# WalkerStalkerv03.net
KiCad netlist of a schematic drawn in EAGLE
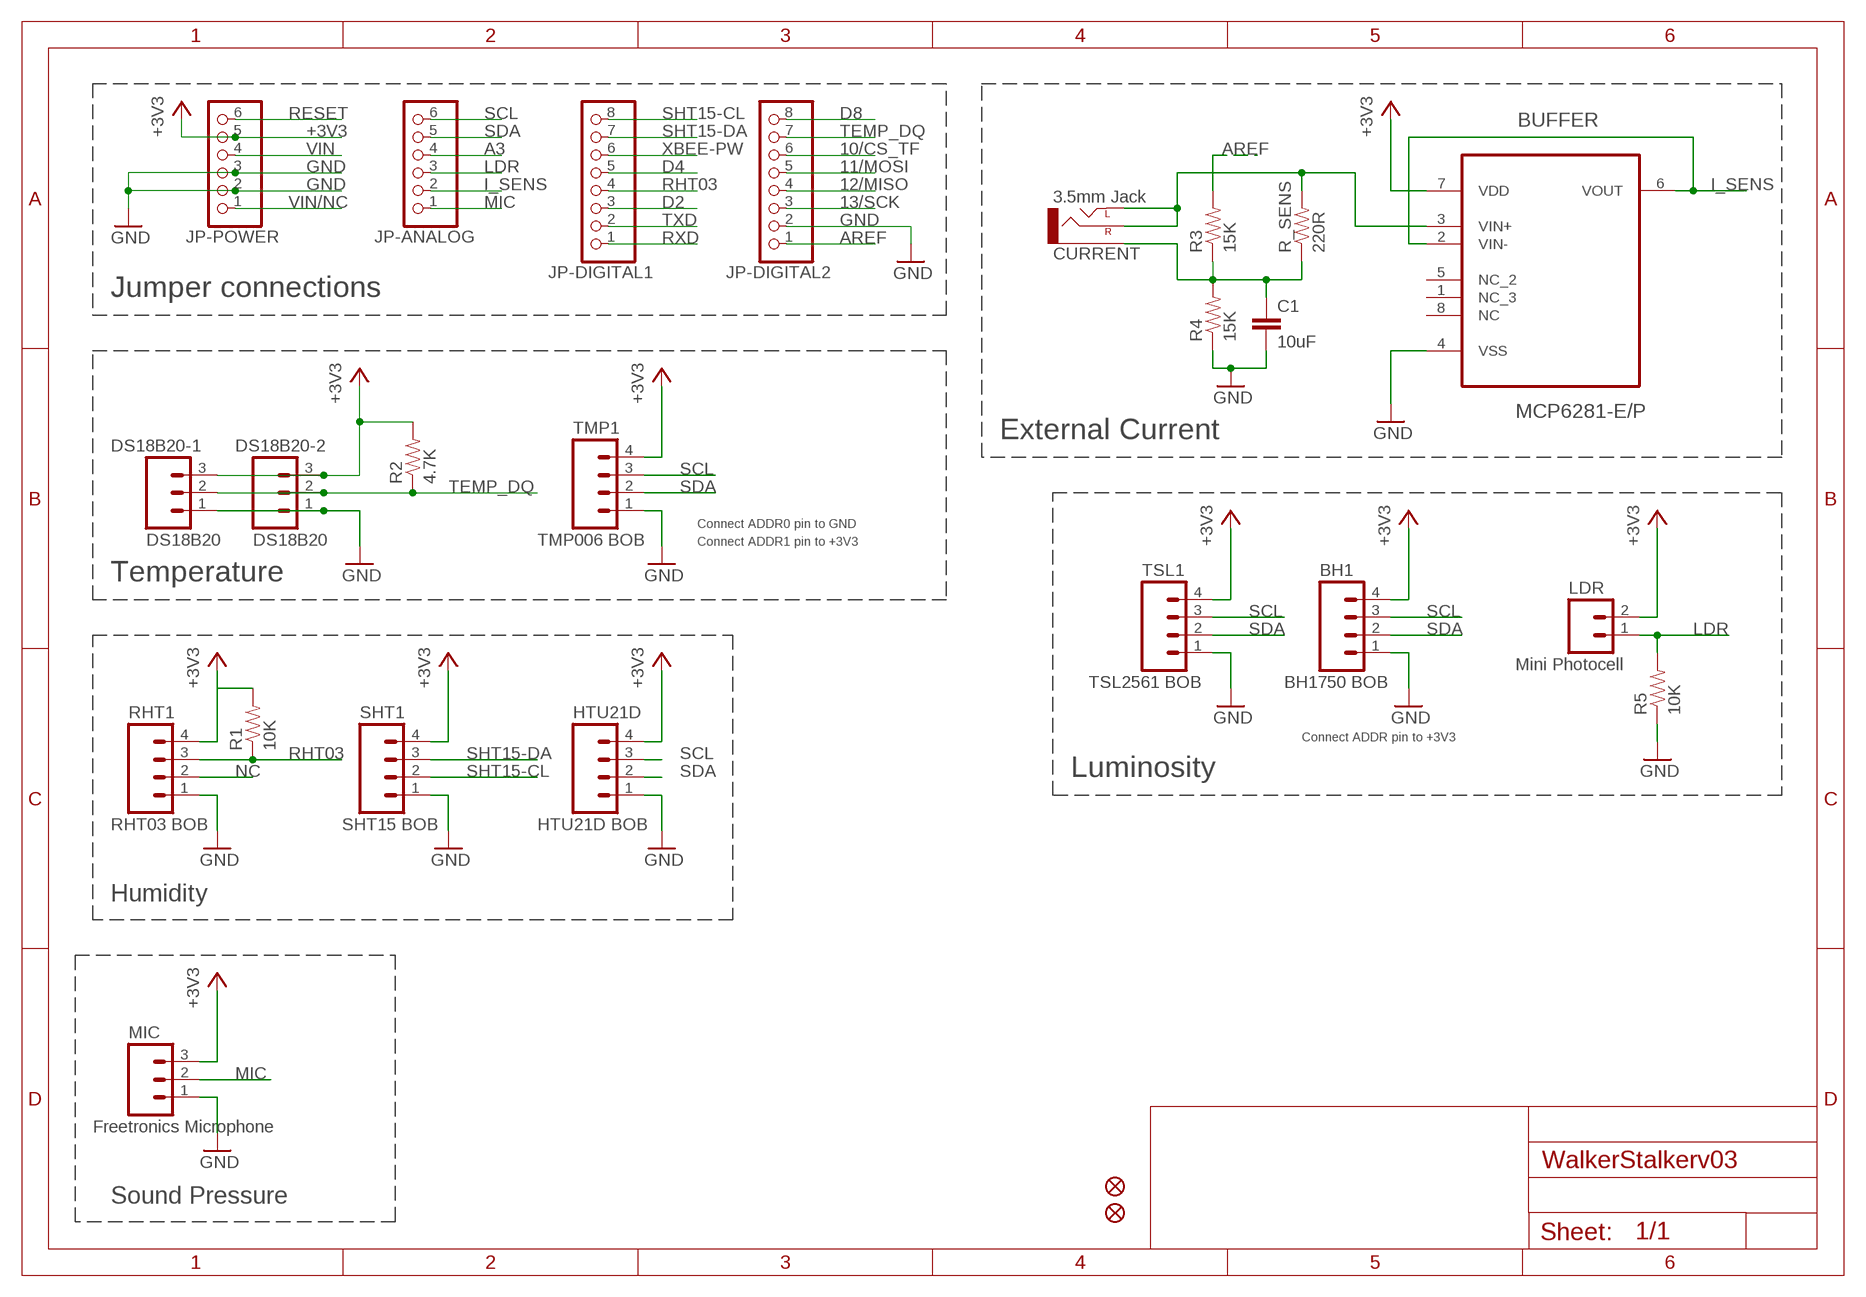
[diagram p0: schematic, sheet 1, part 1 of 2]
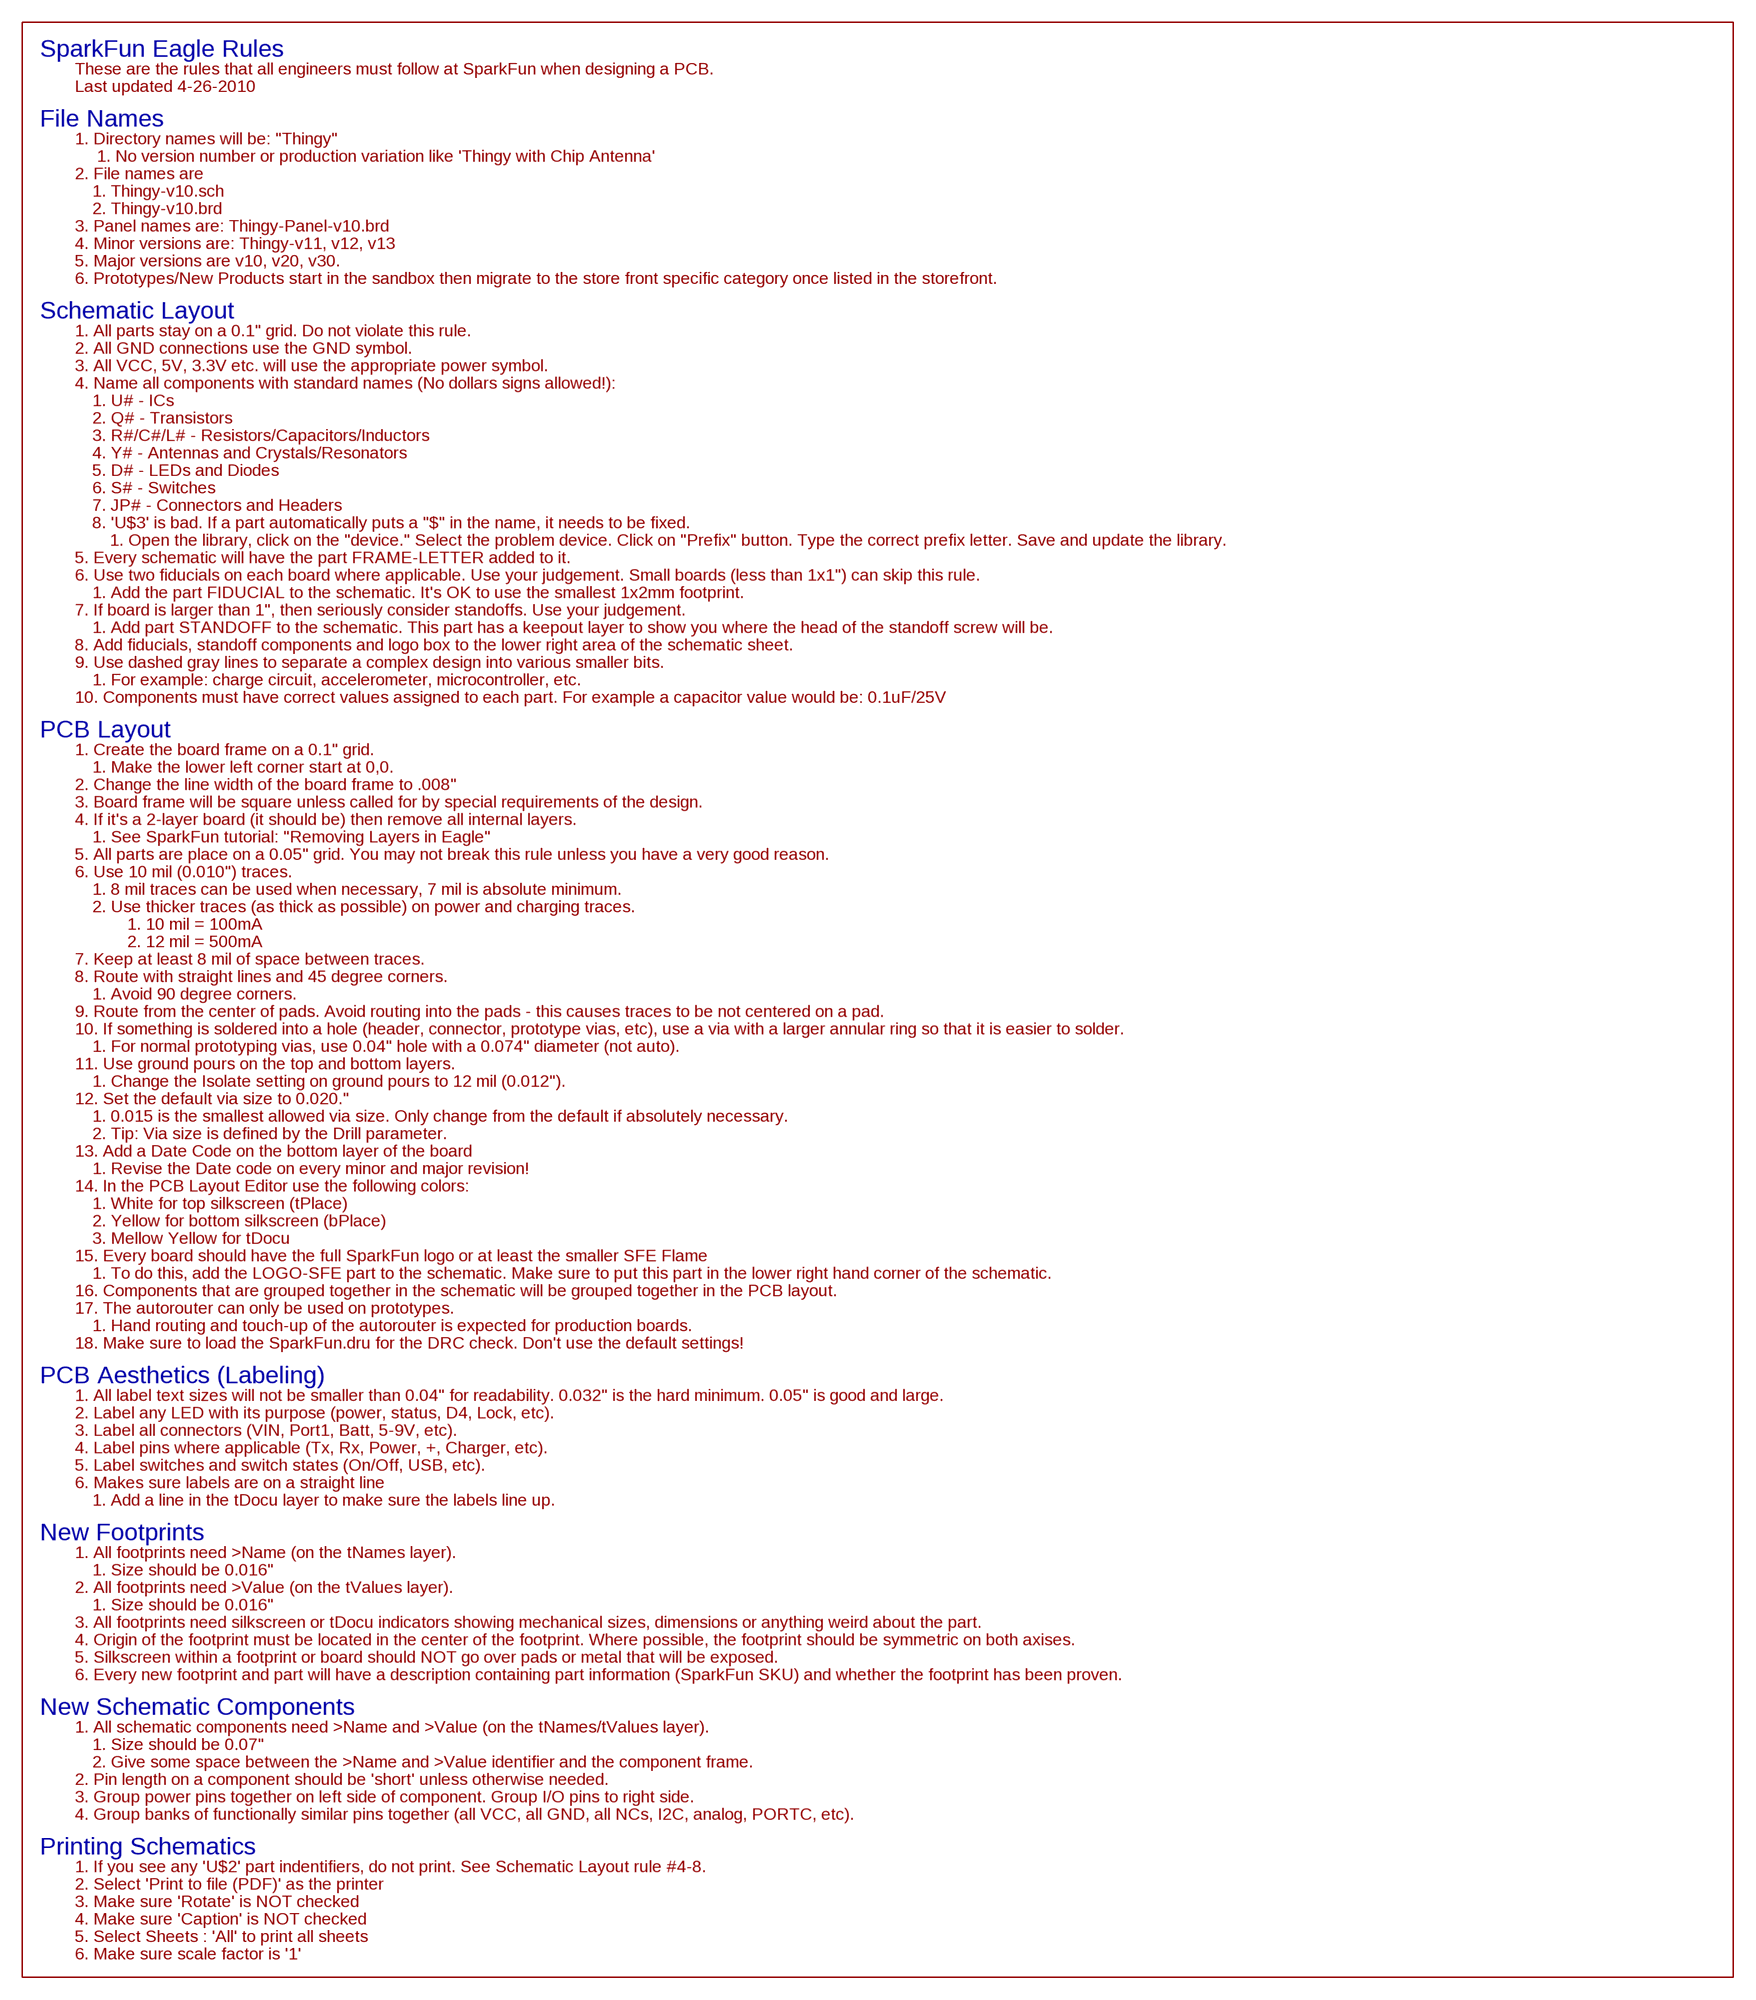
[diagram p1: schematic, sheet 1, part 2 of 2]

(export (version "E")
  (design (tool "Eeschema 10.0.6"))
  (components
    (comp (ref "BH1")
      (value "BH1750 BOB")
      (footprint "eagle-import:MOLEX-1X4")
      (libsource (lib "eagle-import") (part "M04POLAR"))
    )
    (comp (ref "BUFFER")
      (value "MCP6281-E/P")
      (footprint "eagle-import:DIP254P762X432-8")
      (libsource (lib "eagle-import") (part "MCP6281-E/P"))
    )
    (comp (ref "C1")
      (value "10uF")
      (footprint "eagle-import:1206")
      (libsource (lib "eagle-import") (part "CAP1206"))
    )
    (comp (ref "CURRENT")
      (value "3.5mm Jack")
      (footprint "eagle-import:AUDIO-JACK")
      (libsource (lib "eagle-import") (part "AUDIO-JACKPTH"))
    )
    (comp (ref "DS18B20-1")
      (value "DS18B20")
      (footprint "eagle-import:MOLEX-1X3")
      (libsource (lib "eagle-import") (part "M03POLAR"))
    )
    (comp (ref "DS18B20-2")
      (value "DS18B20")
      (footprint "eagle-import:MOLEX-1X3")
      (libsource (lib "eagle-import") (part "M03POLAR"))
    )
    (comp (ref "FID1")
      (value "FIDUCIAL1.5X3")
      (footprint "eagle-import:FIDUCIAL-1.5X3")
      (libsource (lib "eagle-import") (part "FIDUCIAL1.5X3"))
    )
    (comp (ref "FID2")
      (value "FIDUCIAL1.5X3")
      (footprint "eagle-import:FIDUCIAL-1.5X3")
      (libsource (lib "eagle-import") (part "FIDUCIAL1.5X3"))
    )
    (comp (ref "HTU21D")
      (value "HTU21D BOB")
      (footprint "eagle-import:MOLEX-1X4")
      (libsource (lib "eagle-import") (part "M04POLAR"))
    )
    (comp (ref "JP-ANALOG")
      (value "PINHD-1X6CB")
      (footprint "eagle-import:1X06-CLEANBIG")
      (libsource (lib "eagle-import") (part "PINHD-1X6CB"))
    )
    (comp (ref "JP-DIGITAL1")
      (value "PINHD-1X8CLEANBIG")
      (footprint "eagle-import:1X08-CLEANBIG")
      (libsource (lib "eagle-import") (part "PINHD-1X8CLEANBIG"))
    )
    (comp (ref "JP-DIGITAL2")
      (value "PINHD-1X8CLEANBIG")
      (footprint "eagle-import:1X08-CLEANBIG")
      (libsource (lib "eagle-import") (part "PINHD-1X8CLEANBIG"))
    )
    (comp (ref "JP-POWER")
      (value "PINHD-1X6CB")
      (footprint "eagle-import:1X06-CLEANBIG")
      (libsource (lib "eagle-import") (part "PINHD-1X6CB"))
    )
    (comp (ref "LDR")
      (value "Mini Photocell")
      (footprint "eagle-import:MOLEX-1X2")
      (libsource (lib "eagle-import") (part "M02POLAR"))
    )
    (comp (ref "MIC")
      (value "Freetronics Microphone")
      (footprint "eagle-import:MOLEX-1X3")
      (libsource (lib "eagle-import") (part "M03POLAR"))
    )
    (comp (ref "R1")
      (value "10K")
      (footprint "eagle-import:1206")
      (libsource (lib "eagle-import") (part "RESISTOR1206"))
    )
    (comp (ref "R2")
      (value "4.7K")
      (footprint "eagle-import:1206")
      (libsource (lib "eagle-import") (part "RESISTOR1206"))
    )
    (comp (ref "R3")
      (value "15K")
      (footprint "eagle-import:1206")
      (libsource (lib "eagle-import") (part "RESISTOR1206"))
    )
    (comp (ref "R4")
      (value "15K")
      (footprint "eagle-import:1206")
      (libsource (lib "eagle-import") (part "RESISTOR1206"))
    )
    (comp (ref "R5")
      (value "10K")
      (footprint "eagle-import:1206")
      (libsource (lib "eagle-import") (part "RESISTOR1206"))
    )
    (comp (ref "RHT1")
      (value "RHT03 BOB")
      (footprint "eagle-import:MOLEX-1X4")
      (libsource (lib "eagle-import") (part "M04POLAR"))
    )
    (comp (ref "R_SENS")
      (value "220R")
      (footprint "eagle-import:1206")
      (libsource (lib "eagle-import") (part "RESISTOR1206"))
    )
    (comp (ref "SHT1")
      (value "SHT15 BOB")
      (footprint "eagle-import:MOLEX-1X4")
      (libsource (lib "eagle-import") (part "M04POLAR"))
    )
    (comp (ref "TMP1")
      (value "TMP006 BOB")
      (footprint "eagle-import:MOLEX-1X4")
      (libsource (lib "eagle-import") (part "M04POLAR"))
    )
    (comp (ref "TSL1")
      (value "TSL2561 BOB")
      (footprint "eagle-import:MOLEX-1X4")
      (libsource (lib "eagle-import") (part "M04POLAR"))
    )
  )
  (nets
    (net (code "1") (name "+3V3") (class "Default")
      (node (ref "BH1") (pin "4") (pinfunction "4_4") (pintype "passive"))
      (node (ref "BUFFER") (pin "7") (pinfunction "VDD_7") (pintype "power_in"))
      (node (ref "DS18B20-1") (pin "3") (pinfunction "3_3") (pintype "passive"))
      (node (ref "DS18B20-2") (pin "3") (pinfunction "3_3") (pintype "passive"))
      (node (ref "HTU21D") (pin "4") (pinfunction "4_4") (pintype "passive"))
      (node (ref "JP-POWER") (pin "5") (pinfunction "5_5") (pintype "passive"))
      (node (ref "LDR") (pin "2") (pinfunction "2_2") (pintype "passive"))
      (node (ref "MIC") (pin "3") (pinfunction "3_3") (pintype "passive"))
      (node (ref "R1") (pin "2") (pinfunction "2_2") (pintype "passive"))
      (node (ref "R2") (pin "2") (pinfunction "2_2") (pintype "passive"))
      (node (ref "RHT1") (pin "4") (pinfunction "4_4") (pintype "passive"))
      (node (ref "SHT1") (pin "4") (pinfunction "4_4") (pintype "passive"))
      (node (ref "TMP1") (pin "4") (pinfunction "4_4") (pintype "passive"))
      (node (ref "TSL1") (pin "4") (pinfunction "4_4") (pintype "passive"))
    )
    (net (code "2") (name "/10{slash}CS_TF") (class "Default")
      (node (ref "JP-DIGITAL2") (pin "6") (pinfunction "6_6") (pintype "passive"))
    )
    (net (code "3") (name "/11{slash}MOSI") (class "Default")
      (node (ref "JP-DIGITAL2") (pin "5") (pinfunction "5_5") (pintype "passive"))
    )
    (net (code "4") (name "/12{slash}MISO") (class "Default")
      (node (ref "JP-DIGITAL2") (pin "4") (pinfunction "4_4") (pintype "passive"))
    )
    (net (code "5") (name "/13{slash}SCK") (class "Default")
      (node (ref "JP-DIGITAL2") (pin "3") (pinfunction "3_3") (pintype "passive"))
    )
    (net (code "6") (name "/A3") (class "Default")
      (node (ref "JP-ANALOG") (pin "4") (pinfunction "4_4") (pintype "passive"))
    )
    (net (code "7") (name "/AREF") (class "Default")
      (node (ref "JP-DIGITAL2") (pin "1") (pinfunction "1_1") (pintype "passive"))
      (node (ref "R3") (pin "2") (pinfunction "2_2") (pintype "passive"))
    )
    (net (code "8") (name "/D2") (class "Default")
      (node (ref "JP-DIGITAL1") (pin "3") (pinfunction "3_3") (pintype "passive"))
    )
    (net (code "9") (name "/D4") (class "Default")
      (node (ref "JP-DIGITAL1") (pin "5") (pinfunction "5_5") (pintype "passive"))
    )
    (net (code "10") (name "/D8") (class "Default")
      (node (ref "JP-DIGITAL2") (pin "8") (pinfunction "8_8") (pintype "passive"))
    )
    (net (code "11") (name "/I_SENS") (class "Default")
      (node (ref "BUFFER") (pin "2") (pinfunction "VIN-_2") (pintype "input"))
      (node (ref "BUFFER") (pin "6") (pinfunction "VOUT_6") (pintype "output"))
      (node (ref "JP-ANALOG") (pin "2") (pinfunction "2_2") (pintype "passive"))
    )
    (net (code "12") (name "/LDR") (class "Default")
      (node (ref "JP-ANALOG") (pin "3") (pinfunction "3_3") (pintype "passive"))
      (node (ref "LDR") (pin "1") (pinfunction "1_1") (pintype "passive"))
      (node (ref "R5") (pin "2") (pinfunction "2_2") (pintype "passive"))
    )
    (net (code "13") (name "/MIC") (class "Default")
      (node (ref "JP-ANALOG") (pin "1") (pinfunction "1_1") (pintype "passive"))
      (node (ref "MIC") (pin "2") (pinfunction "2_2") (pintype "passive"))
    )
    (net (code "14") (name "/NC") (class "Default")
      (node (ref "RHT1") (pin "2") (pinfunction "2_2") (pintype "passive"))
    )
    (net (code "15") (name "/RESET") (class "Default")
      (node (ref "JP-POWER") (pin "6") (pinfunction "6_6") (pintype "passive"))
    )
    (net (code "16") (name "/RHT03") (class "Default")
      (node (ref "JP-DIGITAL1") (pin "4") (pinfunction "4_4") (pintype "passive"))
      (node (ref "R1") (pin "1") (pinfunction "1_1") (pintype "passive"))
      (node (ref "RHT1") (pin "3") (pinfunction "3_3") (pintype "passive"))
    )
    (net (code "17") (name "/RXD") (class "Default")
      (node (ref "JP-DIGITAL1") (pin "1") (pinfunction "1_1") (pintype "passive"))
    )
    (net (code "18") (name "/SCL") (class "Default")
      (node (ref "BH1") (pin "3") (pinfunction "3_3") (pintype "passive"))
      (node (ref "HTU21D") (pin "3") (pinfunction "3_3") (pintype "passive"))
      (node (ref "JP-ANALOG") (pin "6") (pinfunction "6_6") (pintype "passive"))
      (node (ref "TMP1") (pin "3") (pinfunction "3_3") (pintype "passive"))
      (node (ref "TSL1") (pin "3") (pinfunction "3_3") (pintype "passive"))
    )
    (net (code "19") (name "/SDA") (class "Default")
      (node (ref "BH1") (pin "2") (pinfunction "2_2") (pintype "passive"))
      (node (ref "HTU21D") (pin "2") (pinfunction "2_2") (pintype "passive"))
      (node (ref "JP-ANALOG") (pin "5") (pinfunction "5_5") (pintype "passive"))
      (node (ref "TMP1") (pin "2") (pinfunction "2_2") (pintype "passive"))
      (node (ref "TSL1") (pin "2") (pinfunction "2_2") (pintype "passive"))
    )
    (net (code "20") (name "/SHT15-CL") (class "Default")
      (node (ref "JP-DIGITAL1") (pin "8") (pinfunction "8_8") (pintype "passive"))
      (node (ref "SHT1") (pin "2") (pinfunction "2_2") (pintype "passive"))
    )
    (net (code "21") (name "/SHT15-DA") (class "Default")
      (node (ref "JP-DIGITAL1") (pin "7") (pinfunction "7_7") (pintype "passive"))
      (node (ref "SHT1") (pin "3") (pinfunction "3_3") (pintype "passive"))
    )
    (net (code "22") (name "/TEMP_DQ") (class "Default")
      (node (ref "DS18B20-1") (pin "2") (pinfunction "2_2") (pintype "passive"))
      (node (ref "DS18B20-2") (pin "2") (pinfunction "2_2") (pintype "passive"))
      (node (ref "JP-DIGITAL2") (pin "7") (pinfunction "7_7") (pintype "passive"))
      (node (ref "R2") (pin "1") (pinfunction "1_1") (pintype "passive"))
    )
    (net (code "23") (name "/TXD") (class "Default")
      (node (ref "JP-DIGITAL1") (pin "2") (pinfunction "2_2") (pintype "passive"))
    )
    (net (code "24") (name "/VIN") (class "Default")
      (node (ref "JP-POWER") (pin "4") (pinfunction "4_4") (pintype "passive"))
    )
    (net (code "25") (name "/VIN{slash}NC") (class "Default")
      (node (ref "JP-POWER") (pin "1") (pinfunction "1_1") (pintype "passive"))
    )
    (net (code "26") (name "/XBEE-PW") (class "Default")
      (node (ref "JP-DIGITAL1") (pin "6") (pinfunction "6_6") (pintype "passive"))
    )
    (net (code "27") (name "GND") (class "Default")
      (node (ref "BH1") (pin "1") (pinfunction "1_1") (pintype "passive"))
      (node (ref "BUFFER") (pin "4") (pinfunction "VSS_4") (pintype "power_in"))
      (node (ref "C1") (pin "2") (pinfunction "2_2") (pintype "passive"))
      (node (ref "DS18B20-1") (pin "1") (pinfunction "1_1") (pintype "passive"))
      (node (ref "DS18B20-2") (pin "1") (pinfunction "1_1") (pintype "passive"))
      (node (ref "HTU21D") (pin "1") (pinfunction "1_1") (pintype "passive"))
      (node (ref "JP-DIGITAL2") (pin "2") (pinfunction "2_2") (pintype "passive"))
      (node (ref "JP-POWER") (pin "2") (pinfunction "2_2") (pintype "passive"))
      (node (ref "JP-POWER") (pin "3") (pinfunction "3_3") (pintype "passive"))
      (node (ref "MIC") (pin "1") (pinfunction "1_1") (pintype "passive"))
      (node (ref "R4") (pin "1") (pinfunction "1_1") (pintype "passive"))
      (node (ref "R5") (pin "1") (pinfunction "1_1") (pintype "passive"))
      (node (ref "RHT1") (pin "1") (pinfunction "1_1") (pintype "passive"))
      (node (ref "SHT1") (pin "1") (pinfunction "1_1") (pintype "passive"))
      (node (ref "TMP1") (pin "1") (pinfunction "1_1") (pintype "passive"))
      (node (ref "TSL1") (pin "1") (pinfunction "1_1") (pintype "passive"))
    )
    (net (code "28") (name "Net-(BUFFER-VIN+)") (class "Default")
      (node (ref "BUFFER") (pin "3") (pinfunction "VIN+_3") (pintype "input"))
      (node (ref "CURRENT") (pin "RING") (pinfunction "RIGHT_RING") (pintype "bidirectional"))
      (node (ref "CURRENT") (pin "TIP") (pinfunction "LEFT_TIP") (pintype "bidirectional"))
      (node (ref "R_SENS") (pin "2") (pinfunction "2_2") (pintype "passive"))
    )
    (net (code "29") (name "Net-(C1-Pad1)") (class "Default")
      (node (ref "C1") (pin "1") (pinfunction "1_1") (pintype "passive"))
      (node (ref "CURRENT") (pin "SLEEVE") (pinfunction "SLEEVE_SLEEVE") (pintype "bidirectional"))
      (node (ref "R3") (pin "1") (pinfunction "1_1") (pintype "passive"))
      (node (ref "R4") (pin "2") (pinfunction "2_2") (pintype "passive"))
      (node (ref "R_SENS") (pin "1") (pinfunction "1_1") (pintype "passive"))
    )
    (net (code "30") (name "unconnected-(BUFFER-NC-Pad8)") (class "Default")
      (node (ref "BUFFER") (pin "8") (pinfunction "NC_8") (pintype "no_connect"))
    )
    (net (code "31") (name "unconnected-(BUFFER-NC_2-Pad5)") (class "Default")
      (node (ref "BUFFER") (pin "5") (pinfunction "NC_2_5") (pintype "no_connect"))
    )
    (net (code "32") (name "unconnected-(BUFFER-NC_3-Pad1)") (class "Default")
      (node (ref "BUFFER") (pin "1") (pinfunction "NC_3_1") (pintype "no_connect"))
    )
  )
)
